# Mainboard.net
KiCad netlist of a schematic drawn in EAGLE
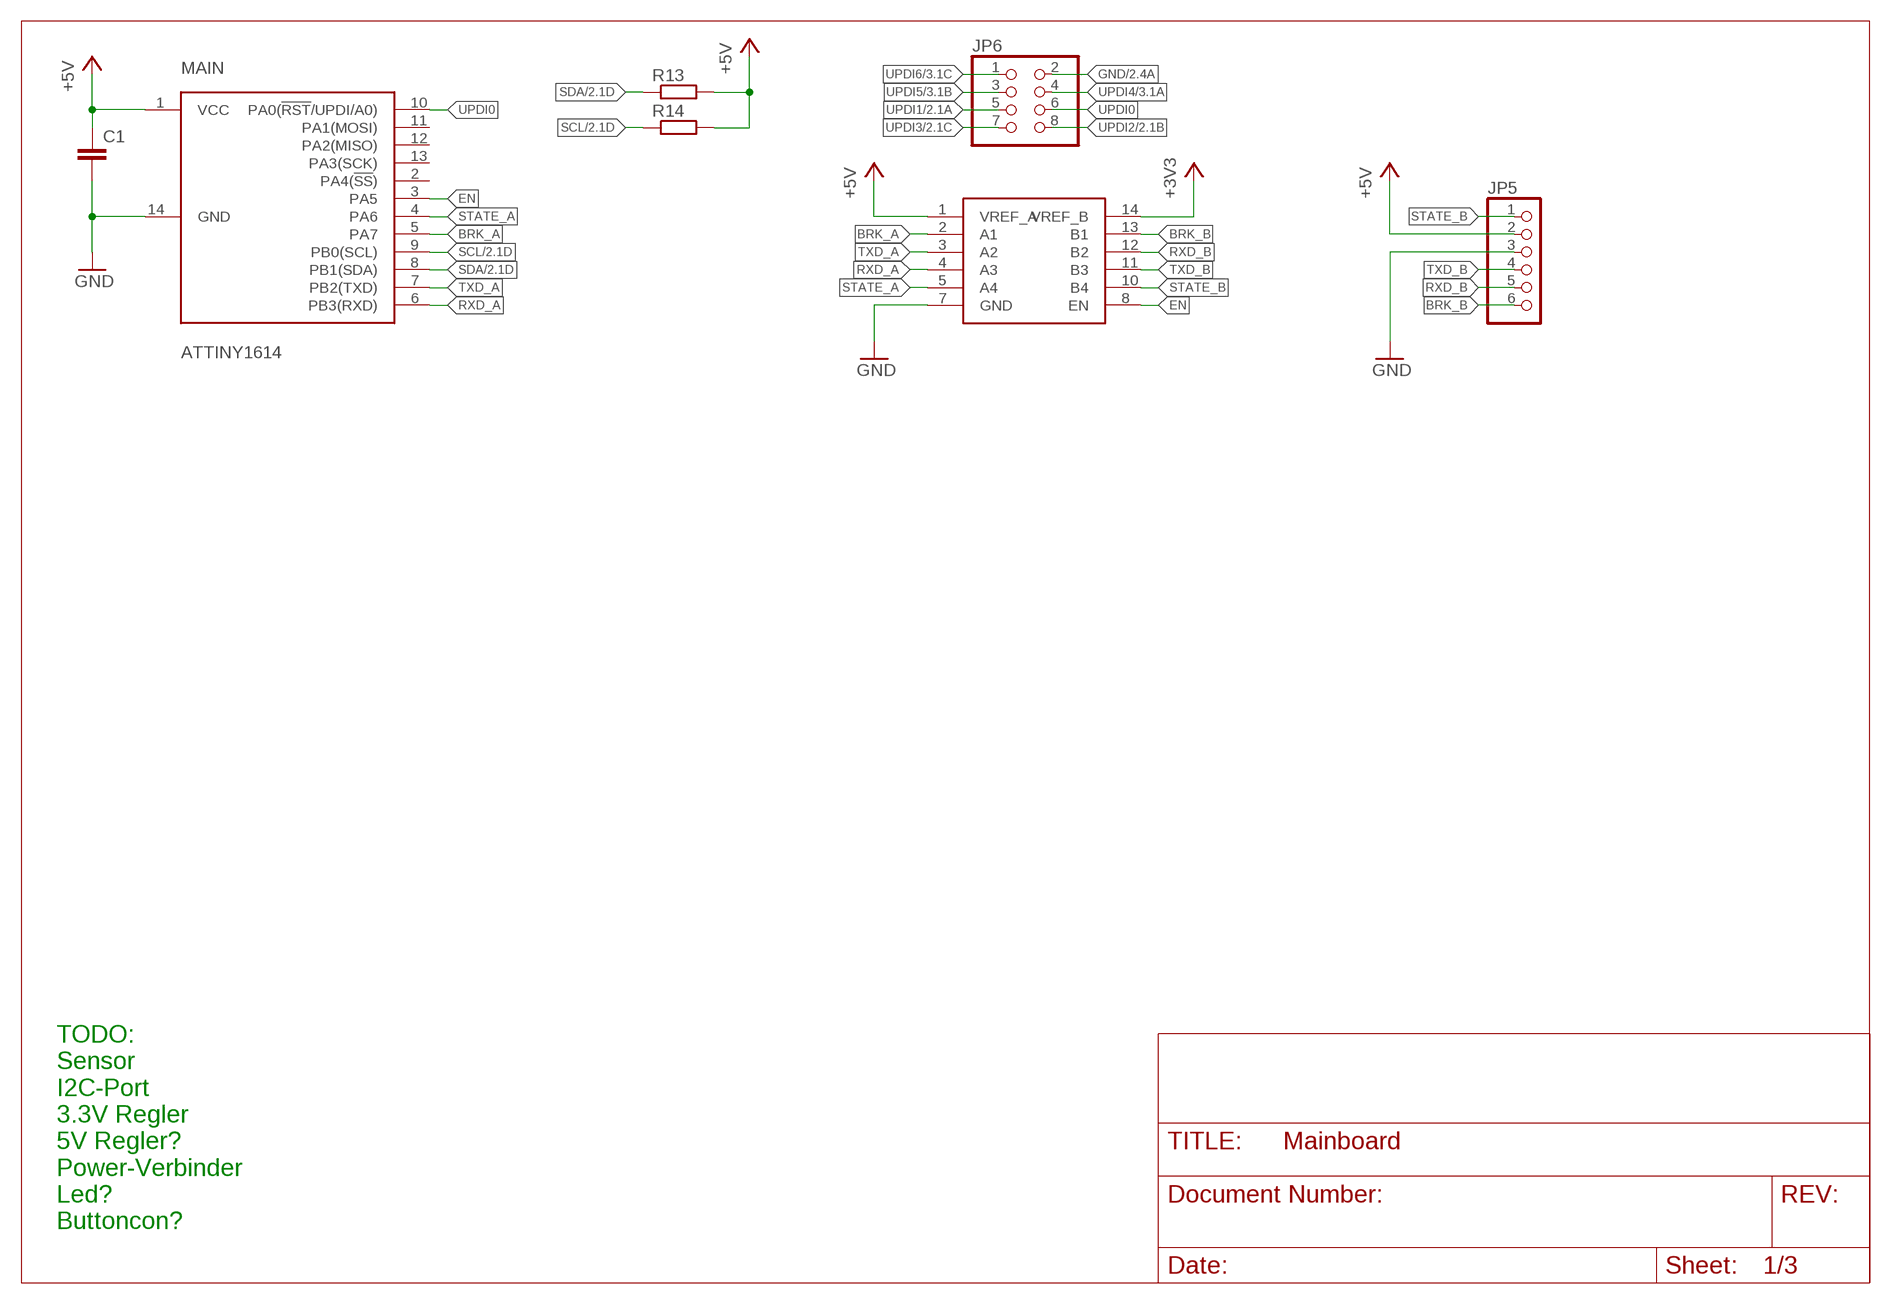
[diagram p0: schematic, sheet 1]
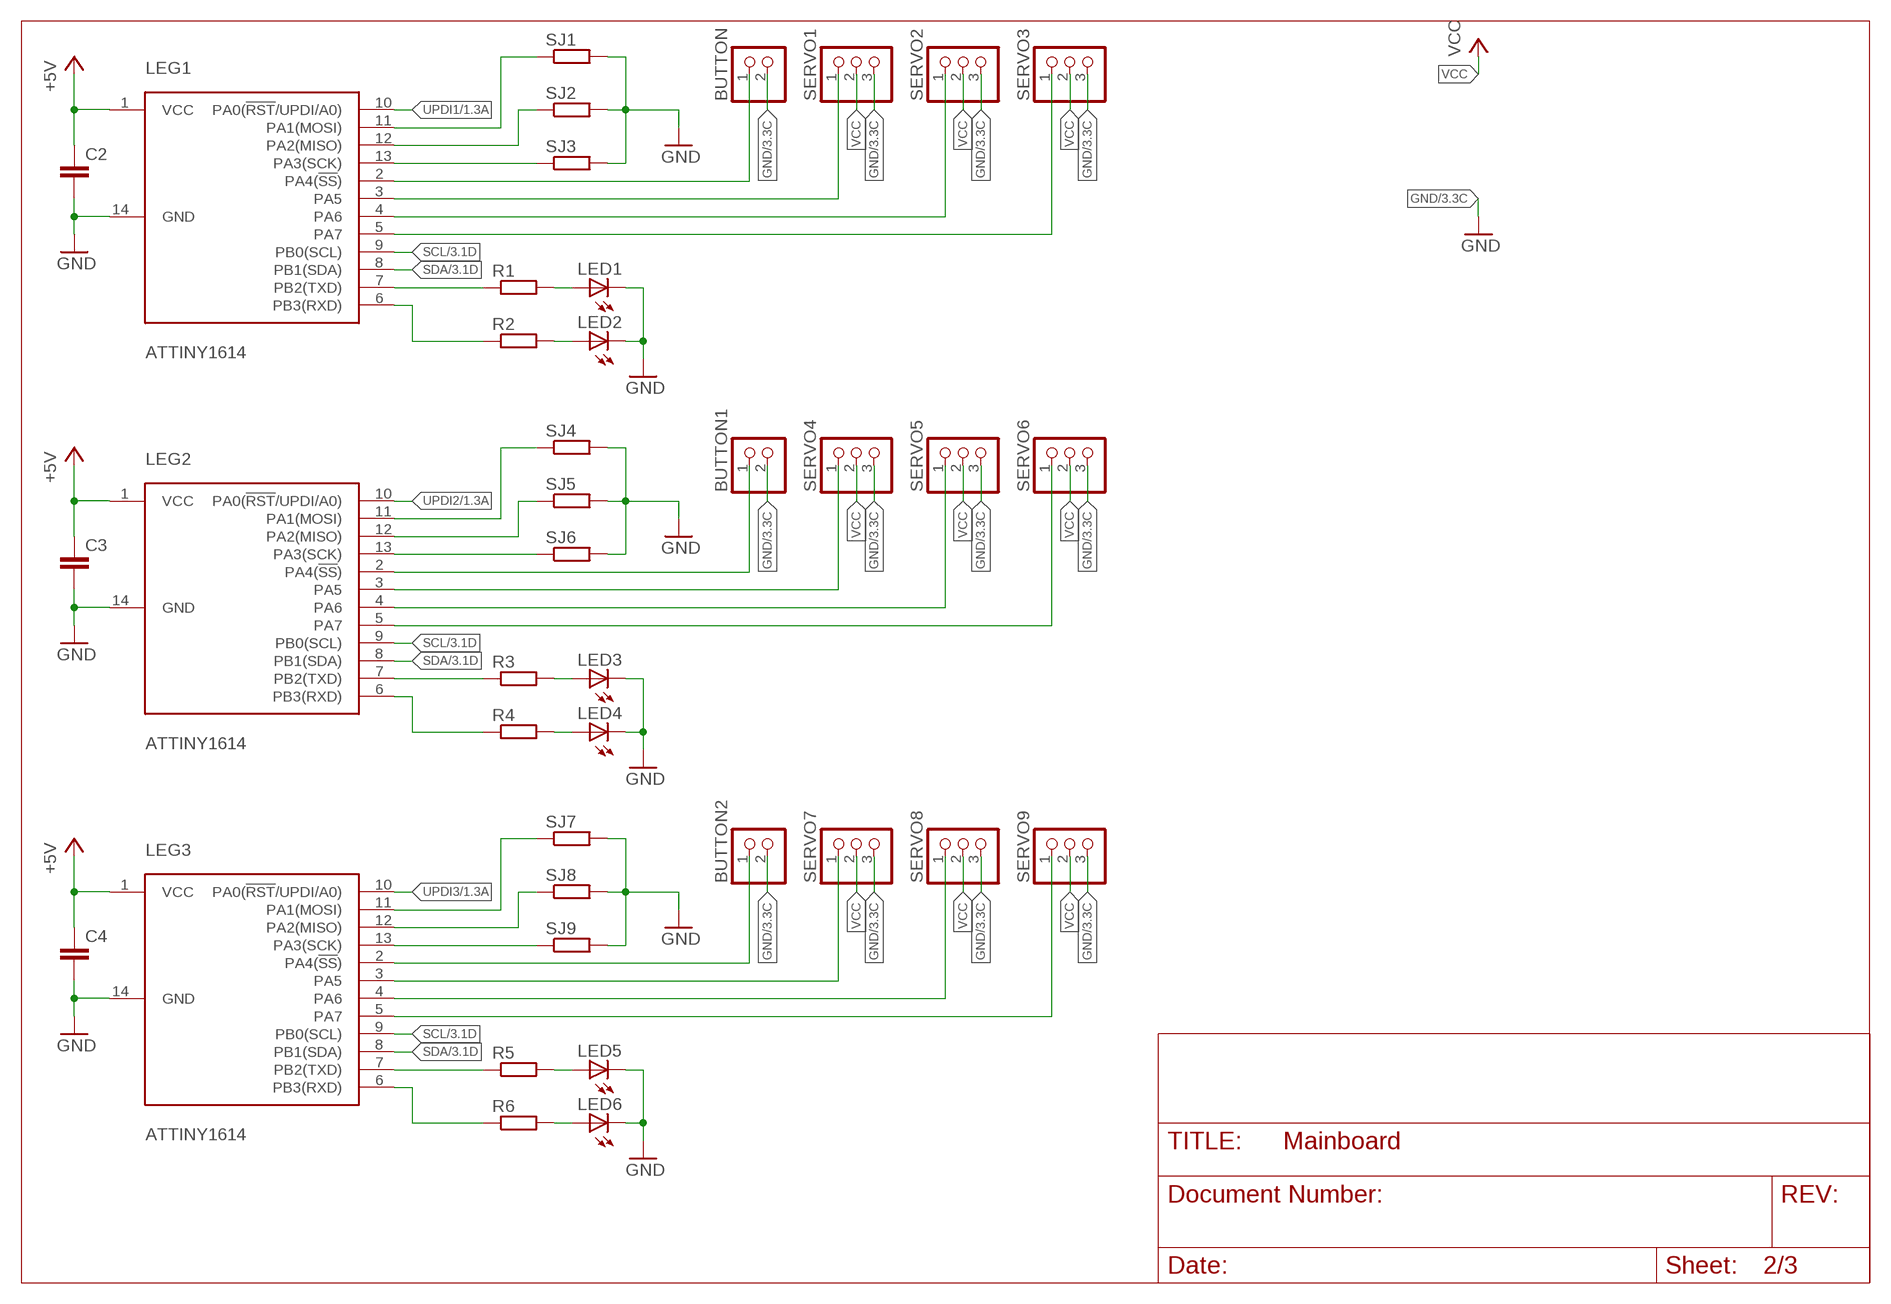
[diagram p1: schematic, sheet 2]
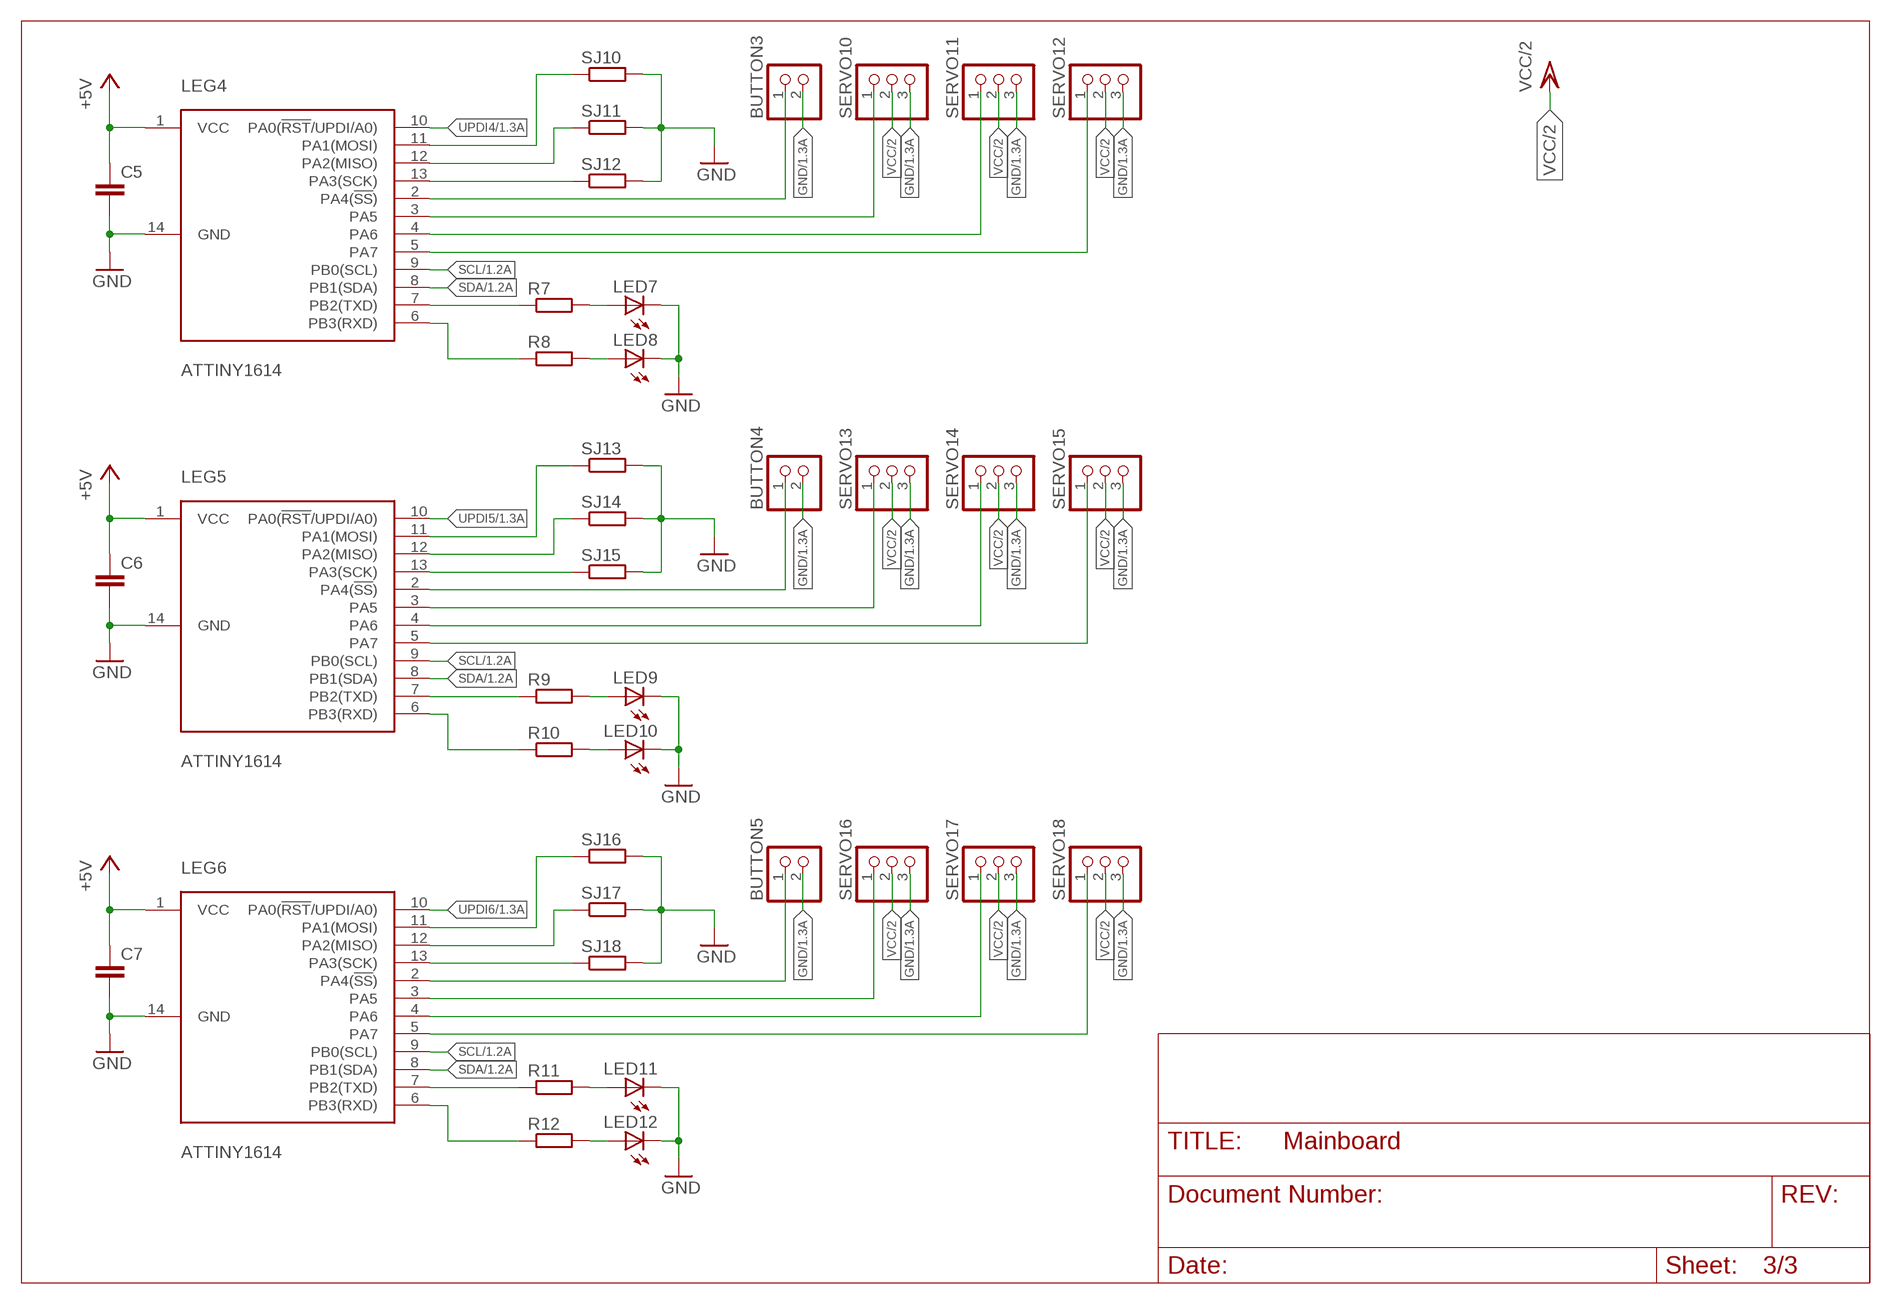
[diagram p2: schematic, sheet 3]

(export (version "E")
  (design (tool "Eeschema 10.0.6"))
  (components
    (comp (ref "BUTTON3")
      (value "PINHD-1X2")
      (footprint "eagle-import:1X02")
      (libsource (lib "eagle-import") (part "PINHD-1X2"))
    )
    (comp (ref "BUTTON4")
      (value "PINHD-1X2")
      (footprint "eagle-import:1X02")
      (libsource (lib "eagle-import") (part "PINHD-1X2"))
    )
    (comp (ref "BUTTON5")
      (value "PINHD-1X2")
      (footprint "eagle-import:1X02")
      (libsource (lib "eagle-import") (part "PINHD-1X2"))
    )
    (comp (ref "C5")
      (value "C-EUC0805")
      (footprint "eagle-import:C0805")
      (libsource (lib "eagle-import") (part "C-EUC0805"))
    )
    (comp (ref "C6")
      (value "C-EUC0805")
      (footprint "eagle-import:C0805")
      (libsource (lib "eagle-import") (part "C-EUC0805"))
    )
    (comp (ref "C7")
      (value "C-EUC0805")
      (footprint "eagle-import:C0805")
      (libsource (lib "eagle-import") (part "C-EUC0805"))
    )
    (comp (ref "LED7")
      (value "LEDCHIP-LED0805")
      (footprint "eagle-import:CHIP-LED0805")
      (libsource (lib "eagle-import") (part "LEDCHIP-LED0805"))
    )
    (comp (ref "LED8")
      (value "LEDCHIP-LED0805")
      (footprint "eagle-import:CHIP-LED0805")
      (libsource (lib "eagle-import") (part "LEDCHIP-LED0805"))
    )
    (comp (ref "LED9")
      (value "LEDCHIP-LED0805")
      (footprint "eagle-import:CHIP-LED0805")
      (libsource (lib "eagle-import") (part "LEDCHIP-LED0805"))
    )
    (comp (ref "LED10")
      (value "LEDCHIP-LED0805")
      (footprint "eagle-import:CHIP-LED0805")
      (libsource (lib "eagle-import") (part "LEDCHIP-LED0805"))
    )
    (comp (ref "LED11")
      (value "LEDCHIP-LED0805")
      (footprint "eagle-import:CHIP-LED0805")
      (libsource (lib "eagle-import") (part "LEDCHIP-LED0805"))
    )
    (comp (ref "LED12")
      (value "LEDCHIP-LED0805")
      (footprint "eagle-import:CHIP-LED0805")
      (libsource (lib "eagle-import") (part "LEDCHIP-LED0805"))
    )
    (comp (ref "LEG4")
      (value "ATTINY1614")
      (footprint "eagle-import:SOIC14")
      (libsource (lib "eagle-import") (part "ATTINY1614/16/17SSNR/SSFR"))
    )
    (comp (ref "LEG5")
      (value "ATTINY1614")
      (footprint "eagle-import:SOIC14")
      (libsource (lib "eagle-import") (part "ATTINY1614/16/17SSNR/SSFR"))
    )
    (comp (ref "LEG6")
      (value "ATTINY1614")
      (footprint "eagle-import:SOIC14")
      (libsource (lib "eagle-import") (part "ATTINY1614/16/17SSNR/SSFR"))
    )
    (comp (ref "R7")
      (value "R-EU_R0805")
      (footprint "eagle-import:R0805")
      (libsource (lib "eagle-import") (part "R-EU_R0805"))
    )
    (comp (ref "R8")
      (value "R-EU_R0805")
      (footprint "eagle-import:R0805")
      (libsource (lib "eagle-import") (part "R-EU_R0805"))
    )
    (comp (ref "R9")
      (value "R-EU_R0805")
      (footprint "eagle-import:R0805")
      (libsource (lib "eagle-import") (part "R-EU_R0805"))
    )
    (comp (ref "R10")
      (value "R-EU_R0805")
      (footprint "eagle-import:R0805")
      (libsource (lib "eagle-import") (part "R-EU_R0805"))
    )
    (comp (ref "R11")
      (value "R-EU_R0805")
      (footprint "eagle-import:R0805")
      (libsource (lib "eagle-import") (part "R-EU_R0805"))
    )
    (comp (ref "R12")
      (value "R-EU_R0805")
      (footprint "eagle-import:R0805")
      (libsource (lib "eagle-import") (part "R-EU_R0805"))
    )
    (comp (ref "SERVO10")
      (value "PINHD-1X3")
      (footprint "eagle-import:1X03")
      (libsource (lib "eagle-import") (part "PINHD-1X3"))
    )
    (comp (ref "SERVO11")
      (value "PINHD-1X3")
      (footprint "eagle-import:1X03")
      (libsource (lib "eagle-import") (part "PINHD-1X3"))
    )
    (comp (ref "SERVO12")
      (value "PINHD-1X3")
      (footprint "eagle-import:1X03")
      (libsource (lib "eagle-import") (part "PINHD-1X3"))
    )
    (comp (ref "SERVO13")
      (value "PINHD-1X3")
      (footprint "eagle-import:1X03")
      (libsource (lib "eagle-import") (part "PINHD-1X3"))
    )
    (comp (ref "SERVO14")
      (value "PINHD-1X3")
      (footprint "eagle-import:1X03")
      (libsource (lib "eagle-import") (part "PINHD-1X3"))
    )
    (comp (ref "SERVO15")
      (value "PINHD-1X3")
      (footprint "eagle-import:1X03")
      (libsource (lib "eagle-import") (part "PINHD-1X3"))
    )
    (comp (ref "SERVO16")
      (value "PINHD-1X3")
      (footprint "eagle-import:1X03")
      (libsource (lib "eagle-import") (part "PINHD-1X3"))
    )
    (comp (ref "SERVO17")
      (value "PINHD-1X3")
      (footprint "eagle-import:1X03")
      (libsource (lib "eagle-import") (part "PINHD-1X3"))
    )
    (comp (ref "SERVO18")
      (value "PINHD-1X3")
      (footprint "eagle-import:1X03")
      (libsource (lib "eagle-import") (part "PINHD-1X3"))
    )
    (comp (ref "SJ10")
      (value "R-EU_R0402")
      (footprint "eagle-import:R0402")
      (libsource (lib "eagle-import") (part "R-EU_R0402"))
    )
    (comp (ref "SJ11")
      (value "R-EU_R0402")
      (footprint "eagle-import:R0402")
      (libsource (lib "eagle-import") (part "R-EU_R0402"))
    )
    (comp (ref "SJ12")
      (value "R-EU_R0402")
      (footprint "eagle-import:R0402")
      (libsource (lib "eagle-import") (part "R-EU_R0402"))
    )
    (comp (ref "SJ13")
      (value "R-EU_R0402")
      (footprint "eagle-import:R0402")
      (libsource (lib "eagle-import") (part "R-EU_R0402"))
    )
    (comp (ref "SJ14")
      (value "R-EU_R0402")
      (footprint "eagle-import:R0402")
      (libsource (lib "eagle-import") (part "R-EU_R0402"))
    )
    (comp (ref "SJ15")
      (value "R-EU_R0402")
      (footprint "eagle-import:R0402")
      (libsource (lib "eagle-import") (part "R-EU_R0402"))
    )
    (comp (ref "SJ16")
      (value "R-EU_R0402")
      (footprint "eagle-import:R0402")
      (libsource (lib "eagle-import") (part "R-EU_R0402"))
    )
    (comp (ref "SJ17")
      (value "R-EU_R0402")
      (footprint "eagle-import:R0402")
      (libsource (lib "eagle-import") (part "R-EU_R0402"))
    )
    (comp (ref "SJ18")
      (value "R-EU_R0402")
      (footprint "eagle-import:R0402")
      (libsource (lib "eagle-import") (part "R-EU_R0402"))
    )
    (comp (ref "BUTTON")
      (value "PINHD-1X2")
      (footprint "eagle-import:1X02")
      (libsource (lib "eagle-import") (part "PINHD-1X2"))
    )
    (comp (ref "BUTTON1")
      (value "PINHD-1X2")
      (footprint "eagle-import:1X02")
      (libsource (lib "eagle-import") (part "PINHD-1X2"))
    )
    (comp (ref "BUTTON2")
      (value "PINHD-1X2")
      (footprint "eagle-import:1X02")
      (libsource (lib "eagle-import") (part "PINHD-1X2"))
    )
    (comp (ref "C2")
      (value "C-EUC0805")
      (footprint "eagle-import:C0805")
      (libsource (lib "eagle-import") (part "C-EUC0805"))
    )
    (comp (ref "C3")
      (value "C-EUC0805")
      (footprint "eagle-import:C0805")
      (libsource (lib "eagle-import") (part "C-EUC0805"))
    )
    (comp (ref "C4")
      (value "C-EUC0805")
      (footprint "eagle-import:C0805")
      (libsource (lib "eagle-import") (part "C-EUC0805"))
    )
    (comp (ref "LED1")
      (value "LEDCHIP-LED0805")
      (footprint "eagle-import:CHIP-LED0805")
      (libsource (lib "eagle-import") (part "LEDCHIP-LED0805"))
    )
    (comp (ref "LED2")
      (value "LEDCHIP-LED0805")
      (footprint "eagle-import:CHIP-LED0805")
      (libsource (lib "eagle-import") (part "LEDCHIP-LED0805"))
    )
    (comp (ref "LED3")
      (value "LEDCHIP-LED0805")
      (footprint "eagle-import:CHIP-LED0805")
      (libsource (lib "eagle-import") (part "LEDCHIP-LED0805"))
    )
    (comp (ref "LED4")
      (value "LEDCHIP-LED0805")
      (footprint "eagle-import:CHIP-LED0805")
      (libsource (lib "eagle-import") (part "LEDCHIP-LED0805"))
    )
    (comp (ref "LED5")
      (value "LEDCHIP-LED0805")
      (footprint "eagle-import:CHIP-LED0805")
      (libsource (lib "eagle-import") (part "LEDCHIP-LED0805"))
    )
    (comp (ref "LED6")
      (value "LEDCHIP-LED0805")
      (footprint "eagle-import:CHIP-LED0805")
      (libsource (lib "eagle-import") (part "LEDCHIP-LED0805"))
    )
    (comp (ref "LEG1")
      (value "ATTINY1614")
      (footprint "eagle-import:SOIC14")
      (libsource (lib "eagle-import") (part "ATTINY1614/16/17SSNR/SSFR"))
    )
    (comp (ref "LEG2")
      (value "ATTINY1614")
      (footprint "eagle-import:SOIC14")
      (libsource (lib "eagle-import") (part "ATTINY1614/16/17SSNR/SSFR"))
    )
    (comp (ref "LEG3")
      (value "ATTINY1614")
      (footprint "eagle-import:SOIC14")
      (libsource (lib "eagle-import") (part "ATTINY1614/16/17SSNR/SSFR"))
    )
    (comp (ref "R1")
      (value "R-EU_R0805")
      (footprint "eagle-import:R0805")
      (libsource (lib "eagle-import") (part "R-EU_R0805"))
    )
    (comp (ref "R2")
      (value "R-EU_R0805")
      (footprint "eagle-import:R0805")
      (libsource (lib "eagle-import") (part "R-EU_R0805"))
    )
    (comp (ref "R3")
      (value "R-EU_R0805")
      (footprint "eagle-import:R0805")
      (libsource (lib "eagle-import") (part "R-EU_R0805"))
    )
    (comp (ref "R4")
      (value "R-EU_R0805")
      (footprint "eagle-import:R0805")
      (libsource (lib "eagle-import") (part "R-EU_R0805"))
    )
    (comp (ref "R5")
      (value "R-EU_R0805")
      (footprint "eagle-import:R0805")
      (libsource (lib "eagle-import") (part "R-EU_R0805"))
    )
    (comp (ref "R6")
      (value "R-EU_R0805")
      (footprint "eagle-import:R0805")
      (libsource (lib "eagle-import") (part "R-EU_R0805"))
    )
    (comp (ref "SERVO1")
      (value "PINHD-1X3")
      (footprint "eagle-import:1X03")
      (libsource (lib "eagle-import") (part "PINHD-1X3"))
    )
    (comp (ref "SERVO2")
      (value "PINHD-1X3")
      (footprint "eagle-import:1X03")
      (libsource (lib "eagle-import") (part "PINHD-1X3"))
    )
    (comp (ref "SERVO3")
      (value "PINHD-1X3")
      (footprint "eagle-import:1X03")
      (libsource (lib "eagle-import") (part "PINHD-1X3"))
    )
    (comp (ref "SERVO4")
      (value "PINHD-1X3")
      (footprint "eagle-import:1X03")
      (libsource (lib "eagle-import") (part "PINHD-1X3"))
    )
    (comp (ref "SERVO5")
      (value "PINHD-1X3")
      (footprint "eagle-import:1X03")
      (libsource (lib "eagle-import") (part "PINHD-1X3"))
    )
    (comp (ref "SERVO6")
      (value "PINHD-1X3")
      (footprint "eagle-import:1X03")
      (libsource (lib "eagle-import") (part "PINHD-1X3"))
    )
    (comp (ref "SERVO7")
      (value "PINHD-1X3")
      (footprint "eagle-import:1X03")
      (libsource (lib "eagle-import") (part "PINHD-1X3"))
    )
    (comp (ref "SERVO8")
      (value "PINHD-1X3")
      (footprint "eagle-import:1X03")
      (libsource (lib "eagle-import") (part "PINHD-1X3"))
    )
    (comp (ref "SERVO9")
      (value "PINHD-1X3")
      (footprint "eagle-import:1X03")
      (libsource (lib "eagle-import") (part "PINHD-1X3"))
    )
    (comp (ref "SJ1")
      (value "R-EU_R0402")
      (footprint "eagle-import:R0402")
      (libsource (lib "eagle-import") (part "R-EU_R0402"))
    )
    (comp (ref "SJ2")
      (value "R-EU_R0402")
      (footprint "eagle-import:R0402")
      (libsource (lib "eagle-import") (part "R-EU_R0402"))
    )
    (comp (ref "SJ3")
      (value "R-EU_R0402")
      (footprint "eagle-import:R0402")
      (libsource (lib "eagle-import") (part "R-EU_R0402"))
    )
    (comp (ref "SJ4")
      (value "R-EU_R0402")
      (footprint "eagle-import:R0402")
      (libsource (lib "eagle-import") (part "R-EU_R0402"))
    )
    (comp (ref "SJ5")
      (value "R-EU_R0402")
      (footprint "eagle-import:R0402")
      (libsource (lib "eagle-import") (part "R-EU_R0402"))
    )
    (comp (ref "SJ6")
      (value "R-EU_R0402")
      (footprint "eagle-import:R0402")
      (libsource (lib "eagle-import") (part "R-EU_R0402"))
    )
    (comp (ref "SJ7")
      (value "R-EU_R0402")
      (footprint "eagle-import:R0402")
      (libsource (lib "eagle-import") (part "R-EU_R0402"))
    )
    (comp (ref "SJ8")
      (value "R-EU_R0402")
      (footprint "eagle-import:R0402")
      (libsource (lib "eagle-import") (part "R-EU_R0402"))
    )
    (comp (ref "SJ9")
      (value "R-EU_R0402")
      (footprint "eagle-import:R0402")
      (libsource (lib "eagle-import") (part "R-EU_R0402"))
    )
    (comp (ref "C1")
      (value "C-EUC0805")
      (footprint "eagle-import:C0805")
      (libsource (lib "eagle-import") (part "C-EUC0805"))
    )
    (comp (ref "JP5")
      (value "PINHD-1X6")
      (footprint "eagle-import:1X06")
      (libsource (lib "eagle-import") (part "PINHD-1X6"))
    )
    (comp (ref "JP6")
      (value "PINHD-2X4")
      (footprint "eagle-import:2X04")
      (libsource (lib "eagle-import") (part "PINHD-2X4"))
    )
    (comp (ref "MAIN")
      (value "ATTINY1614")
      (footprint "eagle-import:SOIC14")
      (libsource (lib "eagle-import") (part "ATTINY1614/16/17SSNR/SSFR"))
    )
    (comp (ref "R13")
      (value "R-EU_R0805")
      (footprint "eagle-import:R0805")
      (libsource (lib "eagle-import") (part "R-EU_R0805"))
    )
    (comp (ref "R14")
      (value "R-EU_R0805")
      (footprint "eagle-import:R0805")
      (libsource (lib "eagle-import") (part "R-EU_R0805"))
    )
    (comp (ref "U$2")
      (value "LSF0204")
      (footprint "eagle-import:TSSOP14")
      (libsource (lib "eagle-import") (part "LSF0204"))
    )
  )
  (nets
    (net (code "1") (name "+3V3") (class "Default")
      (node (ref "U$2") (pin "14") (pinfunction "VREF_B_14") (pintype "power_in"))
    )
    (net (code "2") (name "+5V") (class "Default")
      (node (ref "C1") (pin "1") (pinfunction "1_1") (pintype "passive"))
      (node (ref "C2") (pin "1") (pinfunction "1_1") (pintype "passive"))
      (node (ref "C3") (pin "1") (pinfunction "1_1") (pintype "passive"))
      (node (ref "C4") (pin "1") (pinfunction "1_1") (pintype "passive"))
      (node (ref "C5") (pin "1") (pinfunction "1_1") (pintype "passive"))
      (node (ref "C6") (pin "1") (pinfunction "1_1") (pintype "passive"))
      (node (ref "C7") (pin "1") (pinfunction "1_1") (pintype "passive"))
      (node (ref "JP5") (pin "2") (pinfunction "2_2") (pintype "passive"))
      (node (ref "LEG1") (pin "1") (pinfunction "VCC_1") (pintype "power_in"))
      (node (ref "LEG2") (pin "1") (pinfunction "VCC_1") (pintype "power_in"))
      (node (ref "LEG3") (pin "1") (pinfunction "VCC_1") (pintype "power_in"))
      (node (ref "LEG4") (pin "1") (pinfunction "VCC_1") (pintype "power_in"))
      (node (ref "LEG5") (pin "1") (pinfunction "VCC_1") (pintype "power_in"))
      (node (ref "LEG6") (pin "1") (pinfunction "VCC_1") (pintype "power_in"))
      (node (ref "MAIN") (pin "1") (pinfunction "VCC_1") (pintype "power_in"))
      (node (ref "R13") (pin "2") (pinfunction "2_2") (pintype "passive"))
      (node (ref "R14") (pin "2") (pinfunction "2_2") (pintype "passive"))
      (node (ref "U$2") (pin "1") (pinfunction "VREF_A_1") (pintype "power_in"))
    )
    (net (code "3") (name "BRK_A") (class "Default")
      (node (ref "MAIN") (pin "5") (pinfunction "PA7_5") (pintype "bidirectional"))
      (node (ref "U$2") (pin "2") (pinfunction "A1_2") (pintype "bidirectional"))
    )
    (net (code "4") (name "BRK_B") (class "Default")
      (node (ref "JP5") (pin "6") (pinfunction "6_6") (pintype "passive"))
      (node (ref "U$2") (pin "13") (pinfunction "B1_13") (pintype "bidirectional"))
    )
    (net (code "5") (name "EN") (class "Default")
      (node (ref "MAIN") (pin "3") (pinfunction "PA5_3") (pintype "bidirectional"))
      (node (ref "U$2") (pin "8") (pinfunction "EN_8") (pintype "bidirectional"))
    )
    (net (code "6") (name "GND") (class "Default")
      (node (ref "BUTTON") (pin "2") (pinfunction "2_2") (pintype "passive"))
      (node (ref "BUTTON1") (pin "2") (pinfunction "2_2") (pintype "passive"))
      (node (ref "BUTTON2") (pin "2") (pinfunction "2_2") (pintype "passive"))
      (node (ref "BUTTON3") (pin "2") (pinfunction "2_2") (pintype "passive"))
      (node (ref "BUTTON4") (pin "2") (pinfunction "2_2") (pintype "passive"))
      (node (ref "BUTTON5") (pin "2") (pinfunction "2_2") (pintype "passive"))
      (node (ref "C1") (pin "2") (pinfunction "2_2") (pintype "passive"))
      (node (ref "C2") (pin "2") (pinfunction "2_2") (pintype "passive"))
      (node (ref "C3") (pin "2") (pinfunction "2_2") (pintype "passive"))
      (node (ref "C4") (pin "2") (pinfunction "2_2") (pintype "passive"))
      (node (ref "C5") (pin "2") (pinfunction "2_2") (pintype "passive"))
      (node (ref "C6") (pin "2") (pinfunction "2_2") (pintype "passive"))
      (node (ref "C7") (pin "2") (pinfunction "2_2") (pintype "passive"))
      (node (ref "JP5") (pin "3") (pinfunction "3_3") (pintype "passive"))
      (node (ref "JP6") (pin "2") (pinfunction "2_2") (pintype "passive"))
      (node (ref "LED1") (pin "C") (pinfunction "C_C") (pintype "passive"))
      (node (ref "LED10") (pin "C") (pinfunction "C_C") (pintype "passive"))
      (node (ref "LED11") (pin "C") (pinfunction "C_C") (pintype "passive"))
      (node (ref "LED12") (pin "C") (pinfunction "C_C") (pintype "passive"))
      (node (ref "LED2") (pin "C") (pinfunction "C_C") (pintype "passive"))
      (node (ref "LED3") (pin "C") (pinfunction "C_C") (pintype "passive"))
      (node (ref "LED4") (pin "C") (pinfunction "C_C") (pintype "passive"))
      (node (ref "LED5") (pin "C") (pinfunction "C_C") (pintype "passive"))
      (node (ref "LED6") (pin "C") (pinfunction "C_C") (pintype "passive"))
      (node (ref "LED7") (pin "C") (pinfunction "C_C") (pintype "passive"))
      (node (ref "LED8") (pin "C") (pinfunction "C_C") (pintype "passive"))
      (node (ref "LED9") (pin "C") (pinfunction "C_C") (pintype "passive"))
      (node (ref "LEG1") (pin "14") (pinfunction "GND_14") (pintype "power_in"))
      (node (ref "LEG2") (pin "14") (pinfunction "GND_14") (pintype "power_in"))
      (node (ref "LEG3") (pin "14") (pinfunction "GND_14") (pintype "power_in"))
      (node (ref "LEG4") (pin "14") (pinfunction "GND_14") (pintype "power_in"))
      (node (ref "LEG5") (pin "14") (pinfunction "GND_14") (pintype "power_in"))
      (node (ref "LEG6") (pin "14") (pinfunction "GND_14") (pintype "power_in"))
      (node (ref "MAIN") (pin "14") (pinfunction "GND_14") (pintype "power_in"))
      (node (ref "SERVO1") (pin "3") (pinfunction "3_3") (pintype "passive"))
      (node (ref "SERVO10") (pin "3") (pinfunction "3_3") (pintype "passive"))
      (node (ref "SERVO11") (pin "3") (pinfunction "3_3") (pintype "passive"))
      (node (ref "SERVO12") (pin "3") (pinfunction "3_3") (pintype "passive"))
      (node (ref "SERVO13") (pin "3") (pinfunction "3_3") (pintype "passive"))
      (node (ref "SERVO14") (pin "3") (pinfunction "3_3") (pintype "passive"))
      (node (ref "SERVO15") (pin "3") (pinfunction "3_3") (pintype "passive"))
      (node (ref "SERVO16") (pin "3") (pinfunction "3_3") (pintype "passive"))
      (node (ref "SERVO17") (pin "3") (pinfunction "3_3") (pintype "passive"))
      (node (ref "SERVO18") (pin "3") (pinfunction "3_3") (pintype "passive"))
      (node (ref "SERVO2") (pin "3") (pinfunction "3_3") (pintype "passive"))
      (node (ref "SERVO3") (pin "3") (pinfunction "3_3") (pintype "passive"))
      (node (ref "SERVO4") (pin "3") (pinfunction "3_3") (pintype "passive"))
      (node (ref "SERVO5") (pin "3") (pinfunction "3_3") (pintype "passive"))
      (node (ref "SERVO6") (pin "3") (pinfunction "3_3") (pintype "passive"))
      (node (ref "SERVO7") (pin "3") (pinfunction "3_3") (pintype "passive"))
      (node (ref "SERVO8") (pin "3") (pinfunction "3_3") (pintype "passive"))
      (node (ref "SERVO9") (pin "3") (pinfunction "3_3") (pintype "passive"))
      (node (ref "SJ1") (pin "2") (pinfunction "2_2") (pintype "passive"))
      (node (ref "SJ10") (pin "2") (pinfunction "2_2") (pintype "passive"))
      (node (ref "SJ11") (pin "2") (pinfunction "2_2") (pintype "passive"))
      (node (ref "SJ12") (pin "2") (pinfunction "2_2") (pintype "passive"))
      (node (ref "SJ13") (pin "2") (pinfunction "2_2") (pintype "passive"))
      (node (ref "SJ14") (pin "2") (pinfunction "2_2") (pintype "passive"))
      (node (ref "SJ15") (pin "2") (pinfunction "2_2") (pintype "passive"))
      (node (ref "SJ16") (pin "2") (pinfunction "2_2") (pintype "passive"))
      (node (ref "SJ17") (pin "2") (pinfunction "2_2") (pintype "passive"))
      (node (ref "SJ18") (pin "2") (pinfunction "2_2") (pintype "passive"))
      (node (ref "SJ2") (pin "2") (pinfunction "2_2") (pintype "passive"))
      (node (ref "SJ3") (pin "2") (pinfunction "2_2") (pintype "passive"))
      (node (ref "SJ4") (pin "2") (pinfunction "2_2") (pintype "passive"))
      (node (ref "SJ5") (pin "2") (pinfunction "2_2") (pintype "passive"))
      (node (ref "SJ6") (pin "2") (pinfunction "2_2") (pintype "passive"))
      (node (ref "SJ7") (pin "2") (pinfunction "2_2") (pintype "passive"))
      (node (ref "SJ8") (pin "2") (pinfunction "2_2") (pintype "passive"))
      (node (ref "SJ9") (pin "2") (pinfunction "2_2") (pintype "passive"))
      (node (ref "U$2") (pin "7") (pinfunction "GND_7") (pintype "power_in"))
    )
    (net (code "7") (name "Net-(LED1-PadA)") (class "Default")
      (node (ref "LED1") (pin "A") (pinfunction "A_A") (pintype "passive"))
      (node (ref "R1") (pin "2") (pinfunction "2_2") (pintype "passive"))
    )
    (net (code "8") (name "Net-(LED2-PadA)") (class "Default")
      (node (ref "LED2") (pin "A") (pinfunction "A_A") (pintype "passive"))
      (node (ref "R2") (pin "2") (pinfunction "2_2") (pintype "passive"))
    )
    (net (code "9") (name "Net-(LED3-PadA)") (class "Default")
      (node (ref "LED3") (pin "A") (pinfunction "A_A") (pintype "passive"))
      (node (ref "R3") (pin "2") (pinfunction "2_2") (pintype "passive"))
    )
    (net (code "10") (name "Net-(LED4-PadA)") (class "Default")
      (node (ref "LED4") (pin "A") (pinfunction "A_A") (pintype "passive"))
      (node (ref "R4") (pin "2") (pinfunction "2_2") (pintype "passive"))
    )
    (net (code "11") (name "Net-(LED5-PadA)") (class "Default")
      (node (ref "LED5") (pin "A") (pinfunction "A_A") (pintype "passive"))
      (node (ref "R5") (pin "2") (pinfunction "2_2") (pintype "passive"))
    )
    (net (code "12") (name "Net-(LED6-PadA)") (class "Default")
      (node (ref "LED6") (pin "A") (pinfunction "A_A") (pintype "passive"))
      (node (ref "R6") (pin "2") (pinfunction "2_2") (pintype "passive"))
    )
    (net (code "13") (name "Net-(LED7-PadA)") (class "Default")
      (node (ref "LED7") (pin "A") (pinfunction "A_A") (pintype "passive"))
      (node (ref "R7") (pin "2") (pinfunction "2_2") (pintype "passive"))
    )
    (net (code "14") (name "Net-(LED8-PadA)") (class "Default")
      (node (ref "LED8") (pin "A") (pinfunction "A_A") (pintype "passive"))
      (node (ref "R8") (pin "2") (pinfunction "2_2") (pintype "passive"))
    )
    (net (code "15") (name "Net-(LED9-PadA)") (class "Default")
      (node (ref "LED9") (pin "A") (pinfunction "A_A") (pintype "passive"))
      (node (ref "R9") (pin "2") (pinfunction "2_2") (pintype "passive"))
    )
    (net (code "16") (name "Net-(LED10-PadA)") (class "Default")
      (node (ref "LED10") (pin "A") (pinfunction "A_A") (pintype "passive"))
      (node (ref "R10") (pin "2") (pinfunction "2_2") (pintype "passive"))
    )
    (net (code "17") (name "Net-(LED11-PadA)") (class "Default")
      (node (ref "LED11") (pin "A") (pinfunction "A_A") (pintype "passive"))
      (node (ref "R11") (pin "2") (pinfunction "2_2") (pintype "passive"))
    )
    (net (code "18") (name "Net-(LED12-PadA)") (class "Default")
      (node (ref "LED12") (pin "A") (pinfunction "A_A") (pintype "passive"))
      (node (ref "R12") (pin "2") (pinfunction "2_2") (pintype "passive"))
    )
    (net (code "19") (name "Net-(LEG1-PA1(MOSI))") (class "Default")
      (node (ref "LEG1") (pin "11") (pinfunction "PA1(MOSI)_11") (pintype "bidirectional"))
      (node (ref "SJ1") (pin "1") (pinfunction "1_1") (pintype "passive"))
    )
    (net (code "20") (name "Net-(LEG1-PA2(MISO))") (class "Default")
      (node (ref "LEG1") (pin "12") (pinfunction "PA2(MISO)_12") (pintype "bidirectional"))
      (node (ref "SJ2") (pin "1") (pinfunction "1_1") (pintype "passive"))
    )
    (net (code "21") (name "Net-(LEG1-PA3(SCK))") (class "Default")
      (node (ref "LEG1") (pin "13") (pinfunction "PA3(SCK)_13") (pintype "bidirectional"))
      (node (ref "SJ3") (pin "1") (pinfunction "1_1") (pintype "passive"))
    )
    (net (code "22") (name "Net-(LEG1-PA4(~{SS}))") (class "Default")
      (node (ref "BUTTON") (pin "1") (pinfunction "1_1") (pintype "passive"))
      (node (ref "LEG1") (pin "2") (pinfunction "PA4(~{SS})_2") (pintype "bidirectional"))
    )
    (net (code "23") (name "Net-(LEG1-PA5)") (class "Default")
      (node (ref "LEG1") (pin "3") (pinfunction "PA5_3") (pintype "bidirectional"))
      (node (ref "SERVO1") (pin "1") (pinfunction "1_1") (pintype "passive"))
    )
    (net (code "24") (name "Net-(LEG1-PA6)") (class "Default")
      (node (ref "LEG1") (pin "4") (pinfunction "PA6_4") (pintype "bidirectional"))
      (node (ref "SERVO2") (pin "1") (pinfunction "1_1") (pintype "passive"))
    )
    (net (code "25") (name "Net-(LEG1-PA7)") (class "Default")
      (node (ref "LEG1") (pin "5") (pinfunction "PA7_5") (pintype "bidirectional"))
      (node (ref "SERVO3") (pin "1") (pinfunction "1_1") (pintype "passive"))
    )
    (net (code "26") (name "Net-(LEG1-PB2(TXD))") (class "Default")
      (node (ref "LEG1") (pin "7") (pinfunction "PB2(TXD)_7") (pintype "bidirectional"))
      (node (ref "R1") (pin "1") (pinfunction "1_1") (pintype "passive"))
    )
    (net (code "27") (name "Net-(LEG1-PB3(RXD))") (class "Default")
      (node (ref "LEG1") (pin "6") (pinfunction "PB3(RXD)_6") (pintype "bidirectional"))
      (node (ref "R2") (pin "1") (pinfunction "1_1") (pintype "passive"))
    )
    (net (code "28") (name "Net-(LEG2-PA1(MOSI))") (class "Default")
      (node (ref "LEG2") (pin "11") (pinfunction "PA1(MOSI)_11") (pintype "bidirectional"))
      (node (ref "SJ4") (pin "1") (pinfunction "1_1") (pintype "passive"))
    )
    (net (code "29") (name "Net-(LEG2-PA2(MISO))") (class "Default")
      (node (ref "LEG2") (pin "12") (pinfunction "PA2(MISO)_12") (pintype "bidirectional"))
      (node (ref "SJ5") (pin "1") (pinfunction "1_1") (pintype "passive"))
    )
    (net (code "30") (name "Net-(LEG2-PA3(SCK))") (class "Default")
      (node (ref "LEG2") (pin "13") (pinfunction "PA3(SCK)_13") (pintype "bidirectional"))
      (node (ref "SJ6") (pin "1") (pinfunction "1_1") (pintype "passive"))
    )
    (net (code "31") (name "Net-(LEG2-PA4(~{SS}))") (class "Default")
      (node (ref "BUTTON1") (pin "1") (pinfunction "1_1") (pintype "passive"))
      (node (ref "LEG2") (pin "2") (pinfunction "PA4(~{SS})_2") (pintype "bidirectional"))
    )
    (net (code "32") (name "Net-(LEG2-PA5)") (class "Default")
      (node (ref "LEG2") (pin "3") (pinfunction "PA5_3") (pintype "bidirectional"))
      (node (ref "SERVO4") (pin "1") (pinfunction "1_1") (pintype "passive"))
    )
    (net (code "33") (name "Net-(LEG2-PA6)") (class "Default")
      (node (ref "LEG2") (pin "4") (pinfunction "PA6_4") (pintype "bidirectional"))
      (node (ref "SERVO5") (pin "1") (pinfunction "1_1") (pintype "passive"))
    )
    (net (code "34") (name "Net-(LEG2-PA7)") (class "Default")
      (node (ref "LEG2") (pin "5") (pinfunction "PA7_5") (pintype "bidirectional"))
      (node (ref "SERVO6") (pin "1") (pinfunction "1_1") (pintype "passive"))
    )
    (net (code "35") (name "Net-(LEG2-PB2(TXD))") (class "Default")
      (node (ref "LEG2") (pin "7") (pinfunction "PB2(TXD)_7") (pintype "bidirectional"))
      (node (ref "R3") (pin "1") (pinfunction "1_1") (pintype "passive"))
    )
    (net (code "36") (name "Net-(LEG2-PB3(RXD))") (class "Default")
      (node (ref "LEG2") (pin "6") (pinfunction "PB3(RXD)_6") (pintype "bidirectional"))
      (node (ref "R4") (pin "1") (pinfunction "1_1") (pintype "passive"))
    )
    (net (code "37") (name "Net-(LEG3-PA1(MOSI))") (class "Default")
      (node (ref "LEG3") (pin "11") (pinfunction "PA1(MOSI)_11") (pintype "bidirectional"))
      (node (ref "SJ7") (pin "1") (pinfunction "1_1") (pintype "passive"))
    )
    (net (code "38") (name "Net-(LEG3-PA2(MISO))") (class "Default")
      (node (ref "LEG3") (pin "12") (pinfunction "PA2(MISO)_12") (pintype "bidirectional"))
      (node (ref "SJ8") (pin "1") (pinfunction "1_1") (pintype "passive"))
    )
    (net (code "39") (name "Net-(LEG3-PA3(SCK))") (class "Default")
      (node (ref "LEG3") (pin "13") (pinfunction "PA3(SCK)_13") (pintype "bidirectional"))
      (node (ref "SJ9") (pin "1") (pinfunction "1_1") (pintype "passive"))
    )
    (net (code "40") (name "Net-(LEG3-PA4(~{SS}))") (class "Default")
      (node (ref "BUTTON2") (pin "1") (pinfunction "1_1") (pintype "passive"))
      (node (ref "LEG3") (pin "2") (pinfunction "PA4(~{SS})_2") (pintype "bidirectional"))
    )
    (net (code "41") (name "Net-(LEG3-PA5)") (class "Default")
      (node (ref "LEG3") (pin "3") (pinfunction "PA5_3") (pintype "bidirectional"))
      (node (ref "SERVO7") (pin "1") (pinfunction "1_1") (pintype "passive"))
    )
    (net (code "42") (name "Net-(LEG3-PA6)") (class "Default")
      (node (ref "LEG3") (pin "4") (pinfunction "PA6_4") (pintype "bidirectional"))
      (node (ref "SERVO8") (pin "1") (pinfunction "1_1") (pintype "passive"))
    )
    (net (code "43") (name "Net-(LEG3-PA7)") (class "Default")
      (node (ref "LEG3") (pin "5") (pinfunction "PA7_5") (pintype "bidirectional"))
      (node (ref "SERVO9") (pin "1") (pinfunction "1_1") (pintype "passive"))
    )
    (net (code "44") (name "Net-(LEG3-PB2(TXD))") (class "Default")
      (node (ref "LEG3") (pin "7") (pinfunction "PB2(TXD)_7") (pintype "bidirectional"))
      (node (ref "R5") (pin "1") (pinfunction "1_1") (pintype "passive"))
    )
    (net (code "45") (name "Net-(LEG3-PB3(RXD))") (class "Default")
      (node (ref "LEG3") (pin "6") (pinfunction "PB3(RXD)_6") (pintype "bidirectional"))
      (node (ref "R6") (pin "1") (pinfunction "1_1") (pintype "passive"))
    )
    (net (code "46") (name "Net-(LEG4-PA1(MOSI))") (class "Default")
      (node (ref "LEG4") (pin "11") (pinfunction "PA1(MOSI)_11") (pintype "bidirectional"))
      (node (ref "SJ10") (pin "1") (pinfunction "1_1") (pintype "passive"))
    )
    (net (code "47") (name "Net-(LEG4-PA2(MISO))") (class "Default")
      (node (ref "LEG4") (pin "12") (pinfunction "PA2(MISO)_12") (pintype "bidirectional"))
      (node (ref "SJ11") (pin "1") (pinfunction "1_1") (pintype "passive"))
    )
    (net (code "48") (name "Net-(LEG4-PA3(SCK))") (class "Default")
      (node (ref "LEG4") (pin "13") (pinfunction "PA3(SCK)_13") (pintype "bidirectional"))
      (node (ref "SJ12") (pin "1") (pinfunction "1_1") (pintype "passive"))
    )
    (net (code "49") (name "Net-(LEG4-PA4(~{SS}))") (class "Default")
      (node (ref "BUTTON3") (pin "1") (pinfunction "1_1") (pintype "passive"))
      (node (ref "LEG4") (pin "2") (pinfunction "PA4(~{SS})_2") (pintype "bidirectional"))
    )
    (net (code "50") (name "Net-(LEG4-PA5)") (class "Default")
      (node (ref "LEG4") (pin "3") (pinfunction "PA5_3") (pintype "bidirectional"))
      (node (ref "SERVO10") (pin "1") (pinfunction "1_1") (pintype "passive"))
    )
    (net (code "51") (name "Net-(LEG4-PA6)") (class "Default")
      (node (ref "LEG4") (pin "4") (pinfunction "PA6_4") (pintype "bidirectional"))
      (node (ref "SERVO11") (pin "1") (pinfunction "1_1") (pintype "passive"))
    )
    (net (code "52") (name "Net-(LEG4-PA7)") (class "Default")
      (node (ref "LEG4") (pin "5") (pinfunction "PA7_5") (pintype "bidirectional"))
      (node (ref "SERVO12") (pin "1") (pinfunction "1_1") (pintype "passive"))
    )
    (net (code "53") (name "Net-(LEG4-PB2(TXD))") (class "Default")
      (node (ref "LEG4") (pin "7") (pinfunction "PB2(TXD)_7") (pintype "bidirectional"))
      (node (ref "R7") (pin "1") (pinfunction "1_1") (pintype "passive"))
    )
    (net (code "54") (name "Net-(LEG4-PB3(RXD))") (class "Default")
      (node (ref "LEG4") (pin "6") (pinfunction "PB3(RXD)_6") (pintype "bidirectional"))
      (node (ref "R8") (pin "1") (pinfunction "1_1") (pintype "passive"))
    )
    (net (code "55") (name "Net-(LEG5-PA1(MOSI))") (class "Default")
      (node (ref "LEG5") (pin "11") (pinfunction "PA1(MOSI)_11") (pintype "bidirectional"))
      (node (ref "SJ13") (pin "1") (pinfunction "1_1") (pintype "passive"))
    )
    (net (code "56") (name "Net-(LEG5-PA2(MISO))") (class "Default")
      (node (ref "LEG5") (pin "12") (pinfunction "PA2(MISO)_12") (pintype "bidirectional"))
      (node (ref "SJ14") (pin "1") (pinfunction "1_1") (pintype "passive"))
    )
    (net (code "57") (name "Net-(LEG5-PA3(SCK))") (class "Default")
      (node (ref "LEG5") (pin "13") (pinfunction "PA3(SCK)_13") (pintype "bidirectional"))
      (node (ref "SJ15") (pin "1") (pinfunction "1_1") (pintype "passive"))
    )
    (net (code "58") (name "Net-(LEG5-PA4(~{SS}))") (class "Default")
      (node (ref "BUTTON4") (pin "1") (pinfunction "1_1") (pintype "passive"))
      (node (ref "LEG5") (pin "2") (pinfunction "PA4(~{SS})_2") (pintype "bidirectional"))
    )
    (net (code "59") (name "Net-(LEG5-PA5)") (class "Default")
      (node (ref "LEG5") (pin "3") (pinfunction "PA5_3") (pintype "bidirectional"))
      (node (ref "SERVO13") (pin "1") (pinfunction "1_1") (pintype "passive"))
    )
    (net (code "60") (name "Net-(LEG5-PA6)") (class "Default")
      (node (ref "LEG5") (pin "4") (pinfunction "PA6_4") (pintype "bidirectional"))
      (node (ref "SERVO14") (pin "1") (pinfunction "1_1") (pintype "passive"))
    )
    (net (code "61") (name "Net-(LEG5-PA7)") (class "Default")
      (node (ref "LEG5") (pin "5") (pinfunction "PA7_5") (pintype "bidirectional"))
      (node (ref "SERVO15") (pin "1") (pinfunction "1_1") (pintype "passive"))
    )
    (net (code "62") (name "Net-(LEG5-PB2(TXD))") (class "Default")
      (node (ref "LEG5") (pin "7") (pinfunction "PB2(TXD)_7") (pintype "bidirectional"))
      (node (ref "R9") (pin "1") (pinfunction "1_1") (pintype "passive"))
    )
    (net (code "63") (name "Net-(LEG5-PB3(RXD))") (class "Default")
      (node (ref "LEG5") (pin "6") (pinfunction "PB3(RXD)_6") (pintype "bidirectional"))
      (node (ref "R10") (pin "1") (pinfunction "1_1") (pintype "passive"))
    )
    (net (code "64") (name "Net-(LEG6-PA1(MOSI))") (class "Default")
      (node (ref "LEG6") (pin "11") (pinfunction "PA1(MOSI)_11") (pintype "bidirectional"))
      (node (ref "SJ16") (pin "1") (pinfunction "1_1") (pintype "passive"))
    )
    (net (code "65") (name "Net-(LEG6-PA2(MISO))") (class "Default")
      (node (ref "LEG6") (pin "12") (pinfunction "PA2(MISO)_12") (pintype "bidirectional"))
      (node (ref "SJ17") (pin "1") (pinfunction "1_1") (pintype "passive"))
    )
    (net (code "66") (name "Net-(LEG6-PA3(SCK))") (class "Default")
      (node (ref "LEG6") (pin "13") (pinfunction "PA3(SCK)_13") (pintype "bidirectional"))
      (node (ref "SJ18") (pin "1") (pinfunction "1_1") (pintype "passive"))
    )
    (net (code "67") (name "Net-(LEG6-PA4(~{SS}))") (class "Default")
      (node (ref "BUTTON5") (pin "1") (pinfunction "1_1") (pintype "passive"))
      (node (ref "LEG6") (pin "2") (pinfunction "PA4(~{SS})_2") (pintype "bidirectional"))
    )
    (net (code "68") (name "Net-(LEG6-PA5)") (class "Default")
      (node (ref "LEG6") (pin "3") (pinfunction "PA5_3") (pintype "bidirectional"))
      (node (ref "SERVO16") (pin "1") (pinfunction "1_1") (pintype "passive"))
    )
    (net (code "69") (name "Net-(LEG6-PA6)") (class "Default")
      (node (ref "LEG6") (pin "4") (pinfunction "PA6_4") (pintype "bidirectional"))
      (node (ref "SERVO17") (pin "1") (pinfunction "1_1") (pintype "passive"))
    )
    (net (code "70") (name "Net-(LEG6-PA7)") (class "Default")
      (node (ref "LEG6") (pin "5") (pinfunction "PA7_5") (pintype "bidirectional"))
      (node (ref "SERVO18") (pin "1") (pinfunction "1_1") (pintype "passive"))
    )
    (net (code "71") (name "Net-(LEG6-PB2(TXD))") (class "Default")
      (node (ref "LEG6") (pin "7") (pinfunction "PB2(TXD)_7") (pintype "bidirectional"))
      (node (ref "R11") (pin "1") (pinfunction "1_1") (pintype "passive"))
    )
    (net (code "72") (name "Net-(LEG6-PB3(RXD))") (class "Default")
      (node (ref "LEG6") (pin "6") (pinfunction "PB3(RXD)_6") (pintype "bidirectional"))
      (node (ref "R12") (pin "1") (pinfunction "1_1") (pintype "passive"))
    )
    (net (code "73") (name "RXD_A") (class "Default")
      (node (ref "MAIN") (pin "6") (pinfunction "PB3(RXD)_6") (pintype "bidirectional"))
      (node (ref "U$2") (pin "4") (pinfunction "A3_4") (pintype "bidirectional"))
    )
    (net (code "74") (name "RXD_B") (class "Default")
      (node (ref "JP5") (pin "5") (pinfunction "5_5") (pintype "passive"))
      (node (ref "U$2") (pin "12") (pinfunction "B2_12") (pintype "bidirectional"))
    )
    (net (code "75") (name "SCL") (class "Default")
      (node (ref "LEG1") (pin "9") (pinfunction "PB0(SCL)_9") (pintype "bidirectional"))
      (node (ref "LEG2") (pin "9") (pinfunction "PB0(SCL)_9") (pintype "bidirectional"))
      (node (ref "LEG3") (pin "9") (pinfunction "PB0(SCL)_9") (pintype "bidirectional"))
      (node (ref "LEG4") (pin "9") (pinfunction "PB0(SCL)_9") (pintype "bidirectional"))
      (node (ref "LEG5") (pin "9") (pinfunction "PB0(SCL)_9") (pintype "bidirectional"))
      (node (ref "LEG6") (pin "9") (pinfunction "PB0(SCL)_9") (pintype "bidirectional"))
      (node (ref "MAIN") (pin "9") (pinfunction "PB0(SCL)_9") (pintype "bidirectional"))
      (node (ref "R14") (pin "1") (pinfunction "1_1") (pintype "passive"))
    )
    (net (code "76") (name "SDA") (class "Default")
      (node (ref "LEG1") (pin "8") (pinfunction "PB1(SDA)_8") (pintype "bidirectional"))
      (node (ref "LEG2") (pin "8") (pinfunction "PB1(SDA)_8") (pintype "bidirectional"))
      (node (ref "LEG3") (pin "8") (pinfunction "PB1(SDA)_8") (pintype "bidirectional"))
      (node (ref "LEG4") (pin "8") (pinfunction "PB1(SDA)_8") (pintype "bidirectional"))
      (node (ref "LEG5") (pin "8") (pinfunction "PB1(SDA)_8") (pintype "bidirectional"))
      (node (ref "LEG6") (pin "8") (pinfunction "PB1(SDA)_8") (pintype "bidirectional"))
      (node (ref "MAIN") (pin "8") (pinfunction "PB1(SDA)_8") (pintype "bidirectional"))
      (node (ref "R13") (pin "1") (pinfunction "1_1") (pintype "passive"))
    )
    (net (code "77") (name "STATE_A") (class "Default")
      (node (ref "MAIN") (pin "4") (pinfunction "PA6_4") (pintype "bidirectional"))
      (node (ref "U$2") (pin "5") (pinfunction "A4_5") (pintype "bidirectional"))
    )
    (net (code "78") (name "STATE_B") (class "Default")
      (node (ref "JP5") (pin "1") (pinfunction "1_1") (pintype "passive"))
      (node (ref "U$2") (pin "10") (pinfunction "B4_10") (pintype "bidirectional"))
    )
    (net (code "79") (name "TXD_A") (class "Default")
      (node (ref "MAIN") (pin "7") (pinfunction "PB2(TXD)_7") (pintype "bidirectional"))
      (node (ref "U$2") (pin "3") (pinfunction "A2_3") (pintype "bidirectional"))
    )
    (net (code "80") (name "TXD_B") (class "Default")
      (node (ref "JP5") (pin "4") (pinfunction "4_4") (pintype "passive"))
      (node (ref "U$2") (pin "11") (pinfunction "B3_11") (pintype "bidirectional"))
    )
    (net (code "81") (name "UPDI0") (class "Default")
      (node (ref "JP6") (pin "6") (pinfunction "6_6") (pintype "passive"))
      (node (ref "MAIN") (pin "10") (pinfunction "PA0(~{RST}/UPDI/A0)_10") (pintype "bidirectional"))
    )
    (net (code "82") (name "UPDI1") (class "Default")
      (node (ref "JP6") (pin "5") (pinfunction "5_5") (pintype "passive"))
      (node (ref "LEG1") (pin "10") (pinfunction "PA0(~{RST}/UPDI/A0)_10") (pintype "bidirectional"))
    )
    (net (code "83") (name "UPDI2") (class "Default")
      (node (ref "JP6") (pin "8") (pinfunction "8_8") (pintype "passive"))
      (node (ref "LEG2") (pin "10") (pinfunction "PA0(~{RST}/UPDI/A0)_10") (pintype "bidirectional"))
    )
    (net (code "84") (name "UPDI3") (class "Default")
      (node (ref "JP6") (pin "7") (pinfunction "7_7") (pintype "passive"))
      (node (ref "LEG3") (pin "10") (pinfunction "PA0(~{RST}/UPDI/A0)_10") (pintype "bidirectional"))
    )
    (net (code "85") (name "UPDI4") (class "Default")
      (node (ref "JP6") (pin "4") (pinfunction "4_4") (pintype "passive"))
      (node (ref "LEG4") (pin "10") (pinfunction "PA0(~{RST}/UPDI/A0)_10") (pintype "bidirectional"))
    )
    (net (code "86") (name "UPDI5") (class "Default")
      (node (ref "JP6") (pin "3") (pinfunction "3_3") (pintype "passive"))
      (node (ref "LEG5") (pin "10") (pinfunction "PA0(~{RST}/UPDI/A0)_10") (pintype "bidirectional"))
    )
    (net (code "87") (name "UPDI6") (class "Default")
      (node (ref "JP6") (pin "1") (pinfunction "1_1") (pintype "passive"))
      (node (ref "LEG6") (pin "10") (pinfunction "PA0(~{RST}/UPDI/A0)_10") (pintype "bidirectional"))
    )
    (net (code "88") (name "VCC") (class "Default")
      (node (ref "SERVO1") (pin "2") (pinfunction "2_2") (pintype "passive"))
      (node (ref "SERVO2") (pin "2") (pinfunction "2_2") (pintype "passive"))
      (node (ref "SERVO3") (pin "2") (pinfunction "2_2") (pintype "passive"))
      (node (ref "SERVO4") (pin "2") (pinfunction "2_2") (pintype "passive"))
      (node (ref "SERVO5") (pin "2") (pinfunction "2_2") (pintype "passive"))
      (node (ref "SERVO6") (pin "2") (pinfunction "2_2") (pintype "passive"))
      (node (ref "SERVO7") (pin "2") (pinfunction "2_2") (pintype "passive"))
      (node (ref "SERVO8") (pin "2") (pinfunction "2_2") (pintype "passive"))
      (node (ref "SERVO9") (pin "2") (pinfunction "2_2") (pintype "passive"))
    )
    (net (code "89") (name "VCC{slash}2") (class "Default")
      (node (ref "SERVO10") (pin "2") (pinfunction "2_2") (pintype "passive"))
      (node (ref "SERVO11") (pin "2") (pinfunction "2_2") (pintype "passive"))
      (node (ref "SERVO12") (pin "2") (pinfunction "2_2") (pintype "passive"))
      (node (ref "SERVO13") (pin "2") (pinfunction "2_2") (pintype "passive"))
      (node (ref "SERVO14") (pin "2") (pinfunction "2_2") (pintype "passive"))
      (node (ref "SERVO15") (pin "2") (pinfunction "2_2") (pintype "passive"))
      (node (ref "SERVO16") (pin "2") (pinfunction "2_2") (pintype "passive"))
      (node (ref "SERVO17") (pin "2") (pinfunction "2_2") (pintype "passive"))
      (node (ref "SERVO18") (pin "2") (pinfunction "2_2") (pintype "passive"))
    )
    (net (code "90") (name "unconnected-(MAIN-PA1(MOSI)-Pad11)") (class "Default")
      (node (ref "MAIN") (pin "11") (pinfunction "PA1(MOSI)_11") (pintype "bidirectional"))
    )
    (net (code "91") (name "unconnected-(MAIN-PA2(MISO)-Pad12)") (class "Default")
      (node (ref "MAIN") (pin "12") (pinfunction "PA2(MISO)_12") (pintype "bidirectional"))
    )
    (net (code "92") (name "unconnected-(MAIN-PA3(SCK)-Pad13)") (class "Default")
      (node (ref "MAIN") (pin "13") (pinfunction "PA3(SCK)_13") (pintype "bidirectional"))
    )
    (net (code "93") (name "unconnected-(MAIN-PA4(~{SS})-Pad2)") (class "Default")
      (node (ref "MAIN") (pin "2") (pinfunction "PA4(~{SS})_2") (pintype "bidirectional"))
    )
  )
)
